# Power.net
KiCad netlist of a schematic drawn in Altium Designer
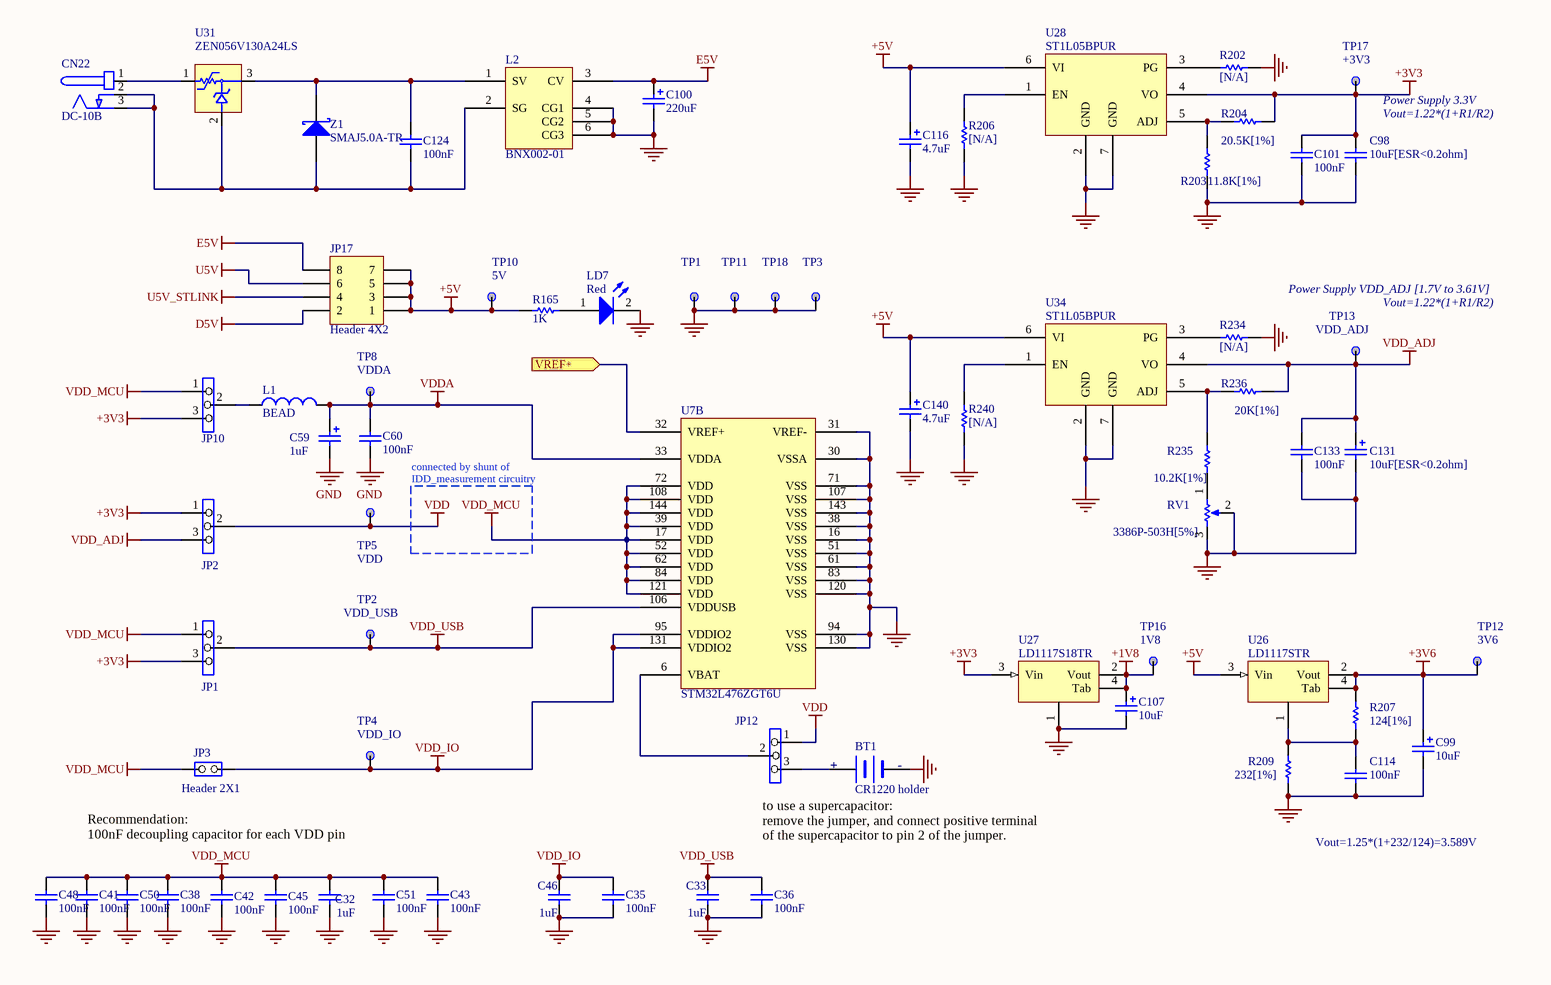
[diagram p0: Power.SchDoc]

(export (version "E")
  (design (tool "Eeschema 10.0.6"))
  (components
    (comp (ref "BT1")
      (value "CR1220 holder")
      (footprint "BAT_2SM_CR1220")
      (description "Battery")
      (libsource (lib "*") (part "BATTERY"))
    )
    (comp (ref "C32")
      (value "1uF")
      (footprint "0603C")
      (description "Capacitor")
      (fields (field (name "PUBLISHER") "Altium Limited"))
      (libsource (lib "Miscellaneous Devices") (part "CAP"))
    )
    (comp (ref "C33")
      (value "1uF")
      (footprint "0603C")
      (description "Capacitor")
      (fields (field (name "PUBLISHER") "Altium Limited"))
      (libsource (lib "Miscellaneous Devices") (part "CAP"))
    )
    (comp (ref "C35")
      (value "100nF")
      (footprint "0402C")
      (description "Capacitor")
      (fields (field (name "PUBLISHER") "Altium Limited"))
      (libsource (lib "Miscellaneous Devices") (part "Cap"))
    )
    (comp (ref "C36")
      (value "100nF")
      (footprint "0402C")
      (description "Capacitor")
      (fields (field (name "PUBLISHER") "Altium Limited"))
      (libsource (lib "Miscellaneous Devices") (part "Cap"))
    )
    (comp (ref "C38")
      (value "100nF")
      (footprint "0402C")
      (description "Capacitor")
      (fields (field (name "PUBLISHER") "Altium Limited"))
      (libsource (lib "Miscellaneous Devices") (part "CAP"))
    )
    (comp (ref "C41")
      (value "100nF")
      (footprint "0402C")
      (description "Capacitor")
      (fields (field (name "PUBLISHER") "Altium Limited"))
      (libsource (lib "Miscellaneous Devices") (part "CAP"))
    )
    (comp (ref "C42")
      (value "100nF")
      (footprint "0402C")
      (description "Capacitor")
      (fields (field (name "PUBLISHER") "Altium Limited"))
      (libsource (lib "Miscellaneous Devices") (part "CAP"))
    )
    (comp (ref "C43")
      (value "100nF")
      (footprint "0402C")
      (description "Capacitor")
      (fields (field (name "PUBLISHER") "Altium Limited"))
      (libsource (lib "Miscellaneous Devices") (part "CAP"))
    )
    (comp (ref "C45")
      (value "100nF")
      (footprint "0402C")
      (description "Capacitor")
      (fields (field (name "PUBLISHER") "Altium Limited"))
      (libsource (lib "Miscellaneous Devices") (part "CAP"))
    )
    (comp (ref "C46")
      (value "1uF")
      (footprint "0603C")
      (description "Capacitor")
      (fields (field (name "PUBLISHER") "Altium Limited"))
      (libsource (lib "Miscellaneous Devices") (part "CAP"))
    )
    (comp (ref "C48")
      (value "100nF")
      (footprint "0402C")
      (description "Capacitor")
      (fields (field (name "PUBLISHER") "Altium Limited"))
      (libsource (lib "Miscellaneous Devices") (part "CAP"))
    )
    (comp (ref "C50")
      (value "100nF")
      (footprint "0402C")
      (description "Capacitor")
      (fields (field (name "PUBLISHER") "Altium Limited"))
      (libsource (lib "Miscellaneous Devices") (part "CAP"))
    )
    (comp (ref "C51")
      (value "100nF")
      (footprint "0402C")
      (description "Capacitor")
      (fields (field (name "PUBLISHER") "Altium Limited"))
      (libsource (lib "Miscellaneous Devices") (part "CAP"))
    )
    (comp (ref "C59")
      (value "1uF")
      (footprint "TAN-A")
      (description "Polarized Capacitor (Radial)")
      (fields (field (name "PUBLISHER") "Altium Limited"))
      (libsource (lib "Miscellaneous Devices") (part "Cap Pol1"))
    )
    (comp (ref "C60")
      (value "100nF")
      (footprint "0402C")
      (description "Capacitor")
      (fields (field (name "PUBLISHER") "Altium Limited"))
      (libsource (lib "Miscellaneous Devices") (part "Cap"))
    )
    (comp (ref "C98")
      (value "10uF[ESR<0.2ohm]")
      (footprint "0805C")
      (description "Capacitor")
      (fields (field (name "PUBLISHER") "Altium Limited"))
      (libsource (lib "Miscellaneous Devices") (part "Cap"))
    )
    (comp (ref "C99")
      (value "10uF")
      (footprint "TAN-A")
      (description "Polarized Capacitor (Radial)")
      (fields (field (name "PUBLISHER") "Altium Limited"))
      (libsource (lib "Miscellaneous Devices") (part "Cap Pol1"))
    )
    (comp (ref "C100")
      (value "220uF")
      (footprint "c310m-6")
      (description "Polarized Capacitor (Radial)")
      (fields (field (name "PUBLISHER") "Altium Limited"))
      (libsource (lib "Miscellaneous Devices") (part "Cap Pol1"))
    )
    (comp (ref "C101")
      (value "100nF")
      (footprint "0402C")
      (description "Capacitor")
      (fields (field (name "PUBLISHER") "Altium Limited"))
      (libsource (lib "Miscellaneous Devices") (part "Cap"))
    )
    (comp (ref "C107")
      (value "10uF")
      (footprint "TAN-A")
      (description "Polarized Capacitor (Radial)")
      (fields (field (name "PUBLISHER") "Altium Limited"))
      (libsource (lib "Miscellaneous Devices") (part "Cap Pol1"))
    )
    (comp (ref "C114")
      (value "100nF")
      (footprint "0402C")
      (description "Capacitor")
      (fields (field (name "PUBLISHER") "Altium Limited"))
      (libsource (lib "Miscellaneous Devices") (part "Cap"))
    )
    (comp (ref "C116")
      (value "4.7uF")
      (footprint "TAN-A")
      (description "Polarized Capacitor (Radial)")
      (fields (field (name "PUBLISHER") "Altium Limited"))
      (libsource (lib "*") (part "Cap Pol1"))
    )
    (comp (ref "C124")
      (value "100nF")
      (footprint "0402C")
      (description "Capacitor")
      (fields (field (name "PUBLISHER") "Altium Limited"))
      (libsource (lib "Miscellaneous Devices") (part "CAP"))
    )
    (comp (ref "C131")
      (value "10uF[ESR<0.2ohm]")
      (footprint "0805C")
      (description "Polarized Capacitor (Radial)")
      (fields (field (name "PUBLISHER") "Altium Limited"))
      (libsource (lib "Miscellaneous Devices") (part "Cap Pol1"))
    )
    (comp (ref "C133")
      (value "100nF")
      (footprint "0402C")
      (description "Capacitor")
      (fields (field (name "PUBLISHER") "Altium Limited"))
      (libsource (lib "Miscellaneous Devices") (part "Cap"))
    )
    (comp (ref "C140")
      (value "4.7uF")
      (footprint "TAN-A")
      (description "Polarized Capacitor (Radial)")
      (fields (field (name "PUBLISHER") "Altium Limited"))
      (libsource (lib "*") (part "Cap Pol1"))
    )
    (comp (ref "CN22")
      (value "DC-10B")
      (footprint "PWR_JACK_DC10")
      (libsource (lib "STR910_SCHLIB") (part "PJ202A"))
    )
    (comp (ref "JP1")
      (value "Header 3X1")
      (footprint "SIP3")
      (libsource (lib "STR910_SCHLIB") (part "Jumper3"))
    )
    (comp (ref "JP2")
      (value "Header 3X1")
      (footprint "SIP3")
      (libsource (lib "STR910_SCHLIB") (part "Jumper3"))
    )
    (comp (ref "JP3") (value "Header 2X1") (footprint "SIP2") (libsource (lib "*") (part "JP2")))
    (comp (ref "JP10")
      (value "Header 3X1")
      (footprint "SIP3")
      (libsource (lib "STR910_SCHLIB") (part "Jumper3"))
    )
    (comp (ref "JP12")
      (value "Header 3X1")
      (footprint "SIP3")
      (libsource (lib "STR910_SCHLIB") (part "Jumper3"))
    )
    (comp (ref "JP17")
      (value "Header 4X2")
      (footprint "HDR_2X4_2R54")
      (description "Header, 4-Pin, Dual row")
      (fields (field (name "PUBLISHER") "Altium Limited"))
      (libsource (lib "Miscellaneous Connectors") (part "Header 4X2"))
    )
    (comp (ref "L1")
      (value "BEAD")
      (footprint "0603L")
      (description "Inductor")
      (fields (field (name "PUBLISHER") "Altium Limited"))
      (libsource (lib "Miscellaneous Devices") (part "Inductor"))
    )
    (comp (ref "L2")
      (value "BNX002-01")
      (footprint "BNX001")
      (libsource (lib "STR910_SCHLIB") (part "BNX002"))
    )
    (comp (ref "LD7")
      (value "Red")
      (footprint "0603D")
      (description "Typical RED, GREEN, YELLOW, AMBER GaAs LED")
      (fields (field (name "PUBLISHER") "Altium Limited"))
      (libsource (lib "Miscellaneous Devices") (part "LED2"))
    )
    (comp (ref "R165")
      (value "1K")
      (footprint "0402R")
      (description "Resistor")
      (fields (field (name "PUBLISHER") "Altium Limited"))
      (libsource (lib "Miscellaneous Devices") (part "res1"))
    )
    (comp (ref "R202")
      (value "[N/A]")
      (footprint "0603R")
      (description "Resistor")
      (fields (field (name "PUBLISHER") "Altium Limited"))
      (libsource (lib "Miscellaneous Devices") (part "res1"))
    )
    (comp (ref "R203")
      (value "11.8K[1%]")
      (footprint "0603R")
      (description "Resistor")
      (fields (field (name "PUBLISHER") "Altium Limited"))
      (libsource (lib "Miscellaneous Devices") (part "Res1"))
    )
    (comp (ref "R204")
      (value "20.5K[1%]")
      (footprint "0603R")
      (description "Resistor")
      (fields (field (name "PUBLISHER") "Altium Limited"))
      (libsource (lib "Miscellaneous Devices") (part "Res1"))
    )
    (comp (ref "R206")
      (value "[N/A]")
      (footprint "0603R")
      (description "Resistor")
      (fields (field (name "PUBLISHER") "Altium Limited"))
      (libsource (lib "Miscellaneous Devices") (part "res1"))
    )
    (comp (ref "R207")
      (value "124[1%]")
      (footprint "0603R")
      (description "Resistor")
      (fields (field (name "PUBLISHER") "Altium Limited"))
      (libsource (lib "Miscellaneous Devices") (part "Res1"))
    )
    (comp (ref "R209")
      (value "232[1%]")
      (footprint "0603R")
      (description "Resistor")
      (fields (field (name "PUBLISHER") "Altium Limited"))
      (libsource (lib "Miscellaneous Devices") (part "Res1"))
    )
    (comp (ref "R234")
      (value "[N/A]")
      (footprint "0603R")
      (description "Resistor")
      (fields (field (name "PUBLISHER") "Altium Limited"))
      (libsource (lib "Miscellaneous Devices") (part "res1"))
    )
    (comp (ref "R235")
      (value "10.2K[1%]")
      (footprint "0603R")
      (description "Resistor")
      (fields (field (name "PUBLISHER") "Altium Limited"))
      (libsource (lib "Miscellaneous Devices") (part "Res1"))
    )
    (comp (ref "R236")
      (value "20K[1%]")
      (footprint "0603R")
      (description "Resistor")
      (fields (field (name "PUBLISHER") "Altium Limited"))
      (libsource (lib "Miscellaneous Devices") (part "Res1"))
    )
    (comp (ref "R240")
      (value "[N/A]")
      (footprint "0603R")
      (description "Resistor")
      (fields (field (name "PUBLISHER") "Altium Limited"))
      (libsource (lib "Miscellaneous Devices") (part "res1"))
    )
    (comp (ref "RV1")
      (value "3386P-503H[5%]")
      (footprint "3386P")
      (description "Potentiometer 50K")
      (libsource (lib "STR910_SCHLIB") (part "RV"))
    )
    (comp (ref "TP1") (value "[N/A]") (footprint "TP") (libsource (lib "*") (part "TP")))
    (comp (ref "TP2")
      (value "[N/A]")
      (footprint "TP")
      (fields (field (name "TP NAME") "VDD_USB"))
      (libsource (lib "*") (part "TP"))
    )
    (comp (ref "TP3") (value "[N/A]") (footprint "TP") (libsource (lib "*") (part "TP")))
    (comp (ref "TP4")
      (value "[N/A]")
      (footprint "TP")
      (fields (field (name "TP NAME") "VDD_IO"))
      (libsource (lib "*") (part "TP"))
    )
    (comp (ref "TP5")
      (value "[N/A]")
      (footprint "TP")
      (fields (field (name "TP NAME") "VDD"))
      (libsource (lib "*") (part "TP"))
    )
    (comp (ref "TP8")
      (value "[N/A]")
      (footprint "TP")
      (fields (field (name "TP NAME") "VDDA"))
      (libsource (lib "*") (part "TP"))
    )
    (comp (ref "TP10")
      (value "[N/A]")
      (footprint "TP")
      (fields (field (name "TP NAME") "5V"))
      (libsource (lib "*") (part "TP"))
    )
    (comp (ref "TP11") (value "[N/A]") (footprint "TP") (libsource (lib "*") (part "TP")))
    (comp (ref "TP12")
      (value "[N/A]")
      (footprint "TP")
      (fields (field (name "TP NAME") "3V6"))
      (libsource (lib "*") (part "TP"))
    )
    (comp (ref "TP13")
      (value "[N/A]")
      (footprint "TP")
      (fields (field (name "TP NAME") "VDD_ADJ"))
      (libsource (lib "*") (part "TP"))
    )
    (comp (ref "TP16")
      (value "[N/A]")
      (footprint "TP")
      (fields (field (name "TP NAME") "1V8"))
      (libsource (lib "*") (part "TP"))
    )
    (comp (ref "TP17")
      (value "[N/A]")
      (footprint "TP")
      (fields (field (name "TP NAME") "+3V3"))
      (libsource (lib "*") (part "TP"))
    )
    (comp (ref "TP18") (value "[N/A]") (footprint "TP") (libsource (lib "*") (part "TP")))
    (comp (ref "U7")
      (value "STM32L476ZGT6U")
      (footprint "TQFP144_0R5_22X22_SOCKET")
      (libsource (lib "MB1144") (part "STM32L476_TQFP144"))
    )
    (comp (ref "U26") (value "LD1117STR") (footprint "SOT-223") (libsource (lib "mb1045") (part "LD1117")))
    (comp (ref "U27") (value "LD1117S18TR") (footprint "SOT-223") (libsource (lib "mb1045") (part "LD1117")))
    (comp (ref "U28")
      (value "ST1L05BPUR")
      (footprint "DFN6_0R95_3X3")
      (libsource (lib "MB1070") (part "ST1L05"))
    )
    (comp (ref "U31")
      (value "ZEN056V130A24LS")
      (footprint "TYCO_ZEN056V130A24LS")
      (libsource (lib "STR910_SCHLIB") (part "ZEN056V130A24LS"))
    )
    (comp (ref "U34")
      (value "ST1L05BPUR")
      (footprint "DFN6_0R95_3X3")
      (libsource (lib "MB1070") (part "ST1L05"))
    )
    (comp (ref "Z1")
      (value "SMAJ5.0A-TR")
      (footprint "sma")
      (description "Schottky Diode")
      (fields (field (name "PUBLISHER") "Altium Limited"))
      (libsource (lib "Miscellaneous Devices") (part "D Schottky"))
    )
  )
  (nets
    (net (code "1") (name "+1V8") (class "Default")
      (node (ref "C107") (pin "1") (pinfunction "1_1") (pintype "passive"))
      (node (ref "TP16") (pin "1") (pinfunction "1_1") (pintype "passive"))
      (node (ref "U27") (pin "2") (pinfunction "Vout_2") (pintype "power_in"))
      (node (ref "U27") (pin "4") (pinfunction "Tab_4") (pintype "power_in"))
    )
    (net (code "2") (name "+3V3") (class "Default")
      (node (ref "C101") (pin "1") (pinfunction "1_1") (pintype "passive"))
      (node (ref "C98") (pin "1") (pinfunction "1_1") (pintype "passive"))
      (node (ref "JP1") (pin "3") (pintype "passive"))
      (node (ref "JP10") (pin "3") (pintype "passive"))
      (node (ref "JP2") (pin "1") (pintype "passive"))
      (node (ref "R204") (pin "1") (pinfunction "1_1") (pintype "passive"))
      (node (ref "TP17") (pin "1") (pinfunction "1_1") (pintype "passive"))
      (node (ref "U27") (pin "3") (pinfunction "Vin_3") (pintype "input"))
      (node (ref "U28") (pin "4") (pinfunction "VO_4") (pintype "passive"))
    )
    (net (code "3") (name "+3V6") (class "Default")
      (node (ref "C99") (pin "1") (pinfunction "1_1") (pintype "passive"))
      (node (ref "R207") (pin "2") (pinfunction "2_2") (pintype "passive"))
      (node (ref "TP12") (pin "1") (pinfunction "1_1") (pintype "passive"))
      (node (ref "U26") (pin "2") (pinfunction "Vout_2") (pintype "power_in"))
      (node (ref "U26") (pin "4") (pinfunction "Tab_4") (pintype "power_in"))
    )
    (net (code "4") (name "+5V") (class "Default")
      (node (ref "C116") (pin "1") (pinfunction "1_1") (pintype "passive"))
      (node (ref "C140") (pin "1") (pinfunction "1_1") (pintype "passive"))
      (node (ref "JP17") (pin "1") (pinfunction "1_1") (pintype "passive"))
      (node (ref "JP17") (pin "3") (pinfunction "3_3") (pintype "passive"))
      (node (ref "JP17") (pin "5") (pinfunction "5_5") (pintype "passive"))
      (node (ref "JP17") (pin "7") (pinfunction "7_7") (pintype "passive"))
      (node (ref "R165") (pin "2") (pinfunction "2_2") (pintype "passive"))
      (node (ref "TP10") (pin "1") (pinfunction "1_1") (pintype "passive"))
      (node (ref "U26") (pin "3") (pinfunction "Vin_3") (pintype "input"))
      (node (ref "U28") (pin "6") (pinfunction "VI_6") (pintype "passive"))
      (node (ref "U34") (pin "6") (pinfunction "VI_6") (pintype "passive"))
    )
    (net (code "5") (name "/VREF+") (class "Default")
      (node (ref "U7") (pin "32") (pinfunction "VREF+_32") (pintype "passive"))
    )
    (net (code "6") (name "D5V") (class "Default")
      (node (ref "JP17") (pin "2") (pinfunction "2_2") (pintype "passive"))
    )
    (net (code "7") (name "E5V") (class "Default")
      (node (ref "C100") (pin "1") (pinfunction "1_1") (pintype "passive"))
      (node (ref "JP17") (pin "8") (pinfunction "8_8") (pintype "passive"))
      (node (ref "L2") (pin "3") (pinfunction "CV_3") (pintype "passive"))
    )
    (net (code "8") (name "GND") (class "Default")
      (node (ref "BT1") (pin "2") (pinfunction "-_2") (pintype "passive"))
      (node (ref "C100") (pin "2") (pinfunction "2_2") (pintype "passive"))
      (node (ref "C101") (pin "2") (pinfunction "2_2") (pintype "passive"))
      (node (ref "C107") (pin "2") (pinfunction "2_2") (pintype "passive"))
      (node (ref "C114") (pin "2") (pinfunction "2_2") (pintype "passive"))
      (node (ref "C116") (pin "2") (pinfunction "2_2") (pintype "passive"))
      (node (ref "C131") (pin "2") (pinfunction "2_2") (pintype "passive"))
      (node (ref "C133") (pin "2") (pinfunction "2_2") (pintype "passive"))
      (node (ref "C140") (pin "2") (pinfunction "2_2") (pintype "passive"))
      (node (ref "C32") (pin "2") (pinfunction "2_2") (pintype "passive"))
      (node (ref "C33") (pin "2") (pinfunction "2_2") (pintype "passive"))
      (node (ref "C35") (pin "1") (pinfunction "1_1") (pintype "passive"))
      (node (ref "C36") (pin "1") (pinfunction "1_1") (pintype "passive"))
      (node (ref "C38") (pin "1") (pinfunction "1_1") (pintype "passive"))
      (node (ref "C41") (pin "1") (pinfunction "1_1") (pintype "passive"))
      (node (ref "C42") (pin "2") (pinfunction "2_2") (pintype "passive"))
      (node (ref "C43") (pin "1") (pinfunction "1_1") (pintype "passive"))
      (node (ref "C45") (pin "2") (pinfunction "2_2") (pintype "passive"))
      (node (ref "C46") (pin "2") (pinfunction "2_2") (pintype "passive"))
      (node (ref "C48") (pin "1") (pinfunction "1_1") (pintype "passive"))
      (node (ref "C50") (pin "1") (pinfunction "1_1") (pintype "passive"))
      (node (ref "C51") (pin "1") (pinfunction "1_1") (pintype "passive"))
      (node (ref "C59") (pin "2") (pinfunction "2_2") (pintype "passive"))
      (node (ref "C60") (pin "1") (pinfunction "1_1") (pintype "passive"))
      (node (ref "C98") (pin "2") (pinfunction "2_2") (pintype "passive"))
      (node (ref "C99") (pin "2") (pinfunction "2_2") (pintype "passive"))
      (node (ref "L2") (pin "4") (pinfunction "CG1_4") (pintype "passive"))
      (node (ref "L2") (pin "5") (pinfunction "CG2_5") (pintype "passive"))
      (node (ref "L2") (pin "6") (pinfunction "CG3_6") (pintype "passive"))
      (node (ref "LD7") (pin "2") (pinfunction "K_2") (pintype "passive"))
      (node (ref "R202") (pin "1") (pinfunction "1_1") (pintype "passive"))
      (node (ref "R203") (pin "2") (pinfunction "2_2") (pintype "passive"))
      (node (ref "R206") (pin "2") (pinfunction "2_2") (pintype "passive"))
      (node (ref "R209") (pin "1") (pinfunction "1_1") (pintype "passive"))
      (node (ref "R234") (pin "1") (pinfunction "1_1") (pintype "passive"))
      (node (ref "R240") (pin "2") (pinfunction "2_2") (pintype "passive"))
      (node (ref "RV1") (pin "2") (pinfunction "TAP_2") (pintype "passive"))
      (node (ref "RV1") (pin "3") (pinfunction "TOP_3") (pintype "passive"))
      (node (ref "TP1") (pin "1") (pinfunction "1_1") (pintype "passive"))
      (node (ref "TP11") (pin "1") (pinfunction "1_1") (pintype "passive"))
      (node (ref "TP18") (pin "1") (pinfunction "1_1") (pintype "passive"))
      (node (ref "TP3") (pin "1") (pinfunction "1_1") (pintype "passive"))
      (node (ref "U27") (pin "1") (pintype "passive"))
      (node (ref "U28") (pin "2") (pinfunction "GND_2") (pintype "passive"))
      (node (ref "U28") (pin "7") (pinfunction "GND_7") (pintype "passive"))
      (node (ref "U34") (pin "2") (pinfunction "GND_2") (pintype "passive"))
      (node (ref "U34") (pin "7") (pinfunction "GND_7") (pintype "passive"))
      (node (ref "U7") (pin "107") (pinfunction "VSS_107") (pintype "passive"))
      (node (ref "U7") (pin "120") (pinfunction "VSS_120") (pintype "passive"))
      (node (ref "U7") (pin "130") (pinfunction "VSS_130") (pintype "passive"))
      (node (ref "U7") (pin "143") (pinfunction "VSS_143") (pintype "passive"))
      (node (ref "U7") (pin "16") (pinfunction "VSS_16") (pintype "passive"))
      (node (ref "U7") (pin "30") (pinfunction "VSSA_30") (pintype "passive"))
      (node (ref "U7") (pin "31") (pinfunction "VREF-_31") (pintype "passive"))
      (node (ref "U7") (pin "38") (pinfunction "VSS_38") (pintype "passive"))
      (node (ref "U7") (pin "51") (pinfunction "VSS_51") (pintype "passive"))
      (node (ref "U7") (pin "61") (pinfunction "VSS_61") (pintype "passive"))
      (node (ref "U7") (pin "71") (pinfunction "VSS_71") (pintype "passive"))
      (node (ref "U7") (pin "83") (pinfunction "VSS_83") (pintype "passive"))
      (node (ref "U7") (pin "94") (pinfunction "VSS_94") (pintype "passive"))
    )
    (net (code "9") (name "Net-(BT1-+)") (class "Default")
      (node (ref "BT1") (pin "1") (pinfunction "+_1") (pintype "passive"))
      (node (ref "JP12") (pin "3") (pintype "passive"))
    )
    (net (code "10") (name "Net-(C114-Pad1)") (class "Default")
      (node (ref "C114") (pin "1") (pinfunction "1_1") (pintype "passive"))
      (node (ref "R207") (pin "1") (pinfunction "1_1") (pintype "passive"))
      (node (ref "R209") (pin "2") (pinfunction "2_2") (pintype "passive"))
      (node (ref "U26") (pin "1") (pintype "passive"))
    )
    (net (code "11") (name "Net-(CN22-+)") (class "Default")
      (node (ref "CN22") (pin "1") (pinfunction "+_1") (pintype "passive"))
      (node (ref "U31") (pin "1") (pintype "passive"))
    )
    (net (code "12") (name "Net-(JP10-Pad2)") (class "Default")
      (node (ref "JP10") (pin "2") (pintype "passive"))
      (node (ref "L1") (pin "1") (pinfunction "1_1") (pintype "passive"))
    )
    (net (code "13") (name "Net-(L2-SG)") (class "Default")
      (node (ref "C124") (pin "2") (pinfunction "2_2") (pintype "passive"))
      (node (ref "CN22") (pin "2") (pinfunction "GND_2") (pintype "passive"))
      (node (ref "CN22") (pin "3") (pinfunction "GND_3") (pintype "passive"))
      (node (ref "L2") (pin "2") (pinfunction "SG_2") (pintype "passive"))
      (node (ref "U31") (pin "2") (pintype "passive"))
      (node (ref "Z1") (pin "1") (pinfunction "A_1") (pintype "passive"))
    )
    (net (code "14") (name "Net-(L2-SV)") (class "Default")
      (node (ref "C124") (pin "1") (pinfunction "1_1") (pintype "passive"))
      (node (ref "L2") (pin "1") (pinfunction "SV_1") (pintype "passive"))
      (node (ref "U31") (pin "3") (pintype "passive"))
      (node (ref "Z1") (pin "2") (pinfunction "K_2") (pintype "passive"))
    )
    (net (code "15") (name "Net-(LD7-A)") (class "Default")
      (node (ref "LD7") (pin "1") (pinfunction "A_1") (pintype "passive"))
      (node (ref "R165") (pin "1") (pinfunction "1_1") (pintype "passive"))
    )
    (net (code "16") (name "Net-(RV1-BOT)") (class "Default")
      (node (ref "R235") (pin "2") (pinfunction "2_2") (pintype "passive"))
      (node (ref "RV1") (pin "1") (pinfunction "BOT_1") (pintype "passive"))
    )
    (net (code "17") (name "Net-(U7B-VBAT)") (class "Default")
      (node (ref "JP12") (pin "2") (pintype "passive"))
      (node (ref "U7") (pin "6") (pinfunction "VBAT_6") (pintype "passive"))
    )
    (net (code "18") (name "Net-(U28-ADJ)") (class "Default")
      (node (ref "R203") (pin "1") (pinfunction "1_1") (pintype "passive"))
      (node (ref "R204") (pin "2") (pinfunction "2_2") (pintype "passive"))
      (node (ref "U28") (pin "5") (pinfunction "ADJ_5") (pintype "passive"))
    )
    (net (code "19") (name "Net-(U28-EN)") (class "Default")
      (node (ref "R206") (pin "1") (pinfunction "1_1") (pintype "passive"))
      (node (ref "U28") (pin "1") (pinfunction "EN_1") (pintype "passive"))
    )
    (net (code "20") (name "Net-(U28-PG)") (class "Default")
      (node (ref "R202") (pin "2") (pinfunction "2_2") (pintype "passive"))
      (node (ref "U28") (pin "3") (pinfunction "PG_3") (pintype "passive"))
    )
    (net (code "21") (name "Net-(U34-ADJ)") (class "Default")
      (node (ref "R235") (pin "1") (pinfunction "1_1") (pintype "passive"))
      (node (ref "R236") (pin "2") (pinfunction "2_2") (pintype "passive"))
      (node (ref "U34") (pin "5") (pinfunction "ADJ_5") (pintype "passive"))
    )
    (net (code "22") (name "Net-(U34-EN)") (class "Default")
      (node (ref "R240") (pin "1") (pinfunction "1_1") (pintype "passive"))
      (node (ref "U34") (pin "1") (pinfunction "EN_1") (pintype "passive"))
    )
    (net (code "23") (name "Net-(U34-PG)") (class "Default")
      (node (ref "R234") (pin "2") (pinfunction "2_2") (pintype "passive"))
      (node (ref "U34") (pin "3") (pinfunction "PG_3") (pintype "passive"))
    )
    (net (code "24") (name "U5V") (class "Default")
      (node (ref "JP17") (pin "6") (pinfunction "6_6") (pintype "passive"))
    )
    (net (code "25") (name "U5V_STLINK") (class "Default")
      (node (ref "JP17") (pin "4") (pinfunction "4_4") (pintype "passive"))
    )
    (net (code "26") (name "VDD") (class "Default")
      (node (ref "JP12") (pin "1") (pintype "passive"))
      (node (ref "JP2") (pin "2") (pintype "passive"))
      (node (ref "TP5") (pin "1") (pinfunction "1_1") (pintype "passive"))
    )
    (net (code "27") (name "VDDA") (class "Default")
      (node (ref "C59") (pin "1") (pinfunction "1_1") (pintype "passive"))
      (node (ref "C60") (pin "2") (pinfunction "2_2") (pintype "passive"))
      (node (ref "L1") (pin "2") (pinfunction "2_2") (pintype "passive"))
      (node (ref "TP8") (pin "1") (pinfunction "1_1") (pintype "passive"))
      (node (ref "U7") (pin "33") (pinfunction "VDDA_33") (pintype "passive"))
    )
    (net (code "28") (name "VDD_ADJ") (class "Default")
      (node (ref "C131") (pin "1") (pinfunction "1_1") (pintype "passive"))
      (node (ref "C133") (pin "1") (pinfunction "1_1") (pintype "passive"))
      (node (ref "JP2") (pin "3") (pintype "passive"))
      (node (ref "R236") (pin "1") (pinfunction "1_1") (pintype "passive"))
      (node (ref "TP13") (pin "1") (pinfunction "1_1") (pintype "passive"))
      (node (ref "U34") (pin "4") (pinfunction "VO_4") (pintype "passive"))
    )
    (net (code "29") (name "VDD_IO") (class "Default")
      (node (ref "C35") (pin "2") (pinfunction "2_2") (pintype "passive"))
      (node (ref "C46") (pin "1") (pinfunction "1_1") (pintype "passive"))
      (node (ref "JP3") (pin "2") (pinfunction "NO_2") (pintype "passive"))
      (node (ref "TP4") (pin "1") (pinfunction "1_1") (pintype "passive"))
      (node (ref "U7") (pin "131") (pinfunction "VDDIO2_131") (pintype "passive"))
      (node (ref "U7") (pin "95") (pinfunction "VDDIO2_95") (pintype "passive"))
    )
    (net (code "30") (name "VDD_MCU") (class "Default")
      (node (ref "C32") (pin "1") (pinfunction "1_1") (pintype "passive"))
      (node (ref "C38") (pin "2") (pinfunction "2_2") (pintype "passive"))
      (node (ref "C41") (pin "2") (pinfunction "2_2") (pintype "passive"))
      (node (ref "C42") (pin "1") (pinfunction "1_1") (pintype "passive"))
      (node (ref "C43") (pin "2") (pinfunction "2_2") (pintype "passive"))
      (node (ref "C45") (pin "1") (pinfunction "1_1") (pintype "passive"))
      (node (ref "C48") (pin "2") (pinfunction "2_2") (pintype "passive"))
      (node (ref "C50") (pin "2") (pinfunction "2_2") (pintype "passive"))
      (node (ref "C51") (pin "2") (pinfunction "2_2") (pintype "passive"))
      (node (ref "JP1") (pin "1") (pintype "passive"))
      (node (ref "JP10") (pin "1") (pintype "passive"))
      (node (ref "JP3") (pin "1") (pinfunction "COMMON_1") (pintype "passive"))
      (node (ref "U7") (pin "108") (pinfunction "VDD_108") (pintype "passive"))
      (node (ref "U7") (pin "121") (pinfunction "VDD_121") (pintype "passive"))
      (node (ref "U7") (pin "144") (pinfunction "VDD_144") (pintype "passive"))
      (node (ref "U7") (pin "17") (pinfunction "VDD_17") (pintype "passive"))
      (node (ref "U7") (pin "39") (pinfunction "VDD_39") (pintype "passive"))
      (node (ref "U7") (pin "52") (pinfunction "VDD_52") (pintype "passive"))
      (node (ref "U7") (pin "62") (pinfunction "VDD_62") (pintype "passive"))
      (node (ref "U7") (pin "72") (pinfunction "VDD_72") (pintype "passive"))
      (node (ref "U7") (pin "84") (pinfunction "VDD_84") (pintype "passive"))
    )
    (net (code "31") (name "VDD_USB") (class "Default")
      (node (ref "C33") (pin "1") (pinfunction "1_1") (pintype "passive"))
      (node (ref "C36") (pin "2") (pinfunction "2_2") (pintype "passive"))
      (node (ref "JP1") (pin "2") (pintype "passive"))
      (node (ref "TP2") (pin "1") (pinfunction "1_1") (pintype "passive"))
      (node (ref "U7") (pin "106") (pinfunction "VDDUSB_106") (pintype "passive"))
    )
  )
)
